# 07_WI-FI.net
KiCad netlist of a schematic drawn in Altium Designer
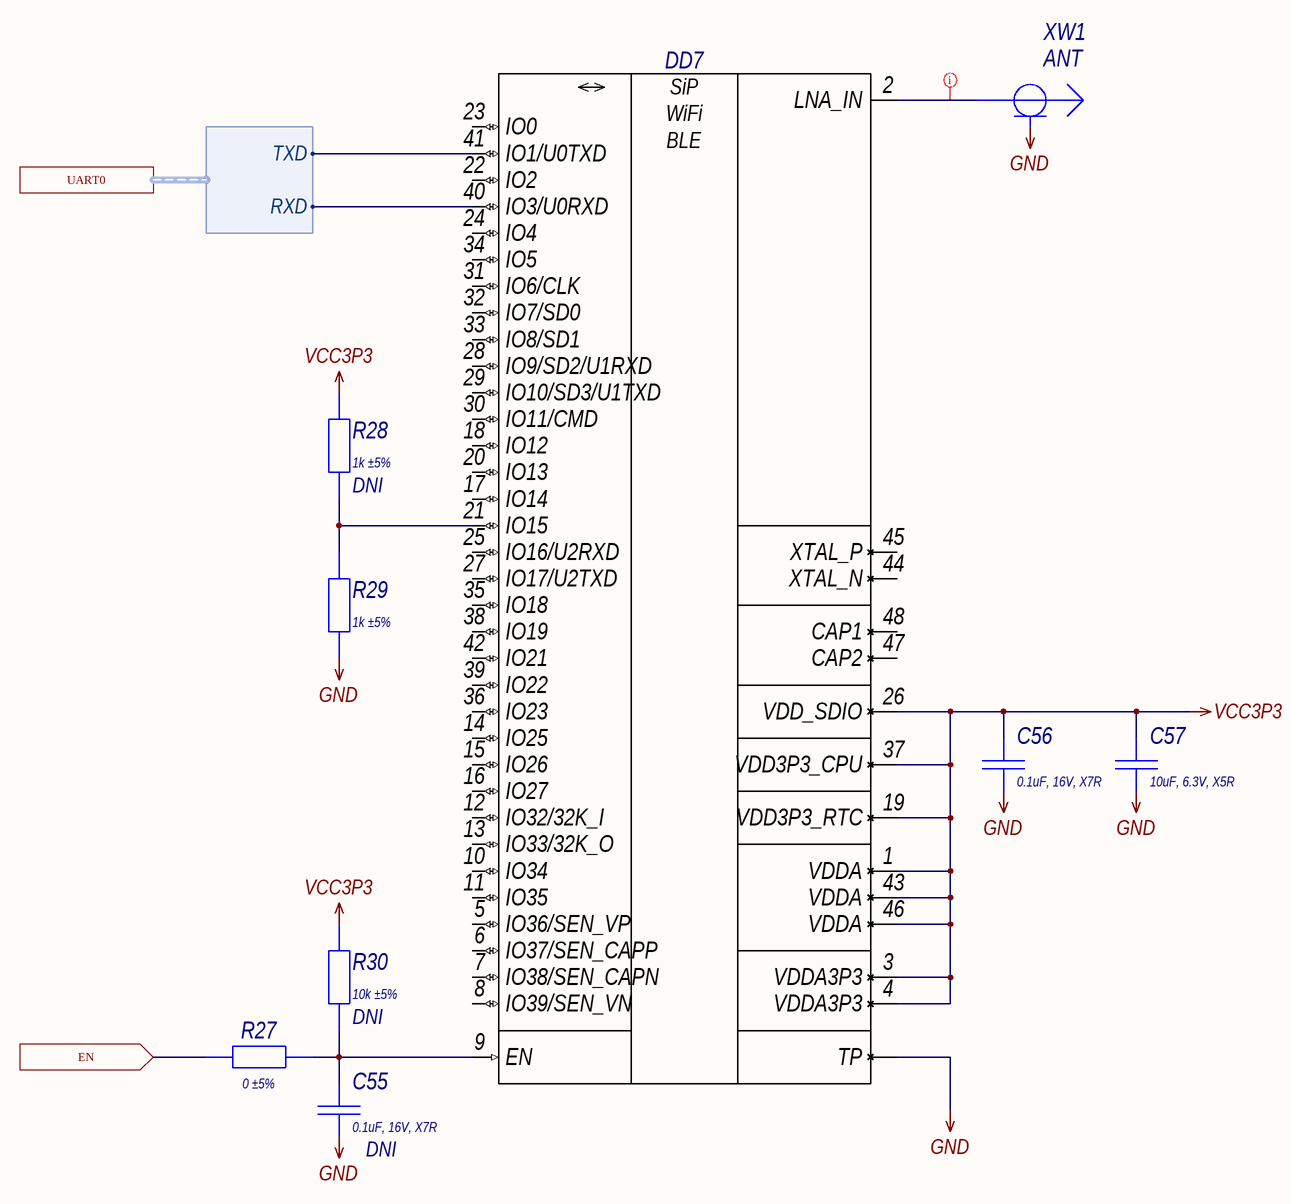
[diagram p0: 07_WI-FI.SchDoc]

(export (version "E")
  (design (tool "Eeschema 10.0.6"))
  (components
    (comp (ref "C55")
      (value "Capacitor")
      (footprint "C0402_L")
      (fields
        (field (name "SCHEMATIC VALUE") "0.1uF, 16V, X7R")
        (field (name "PART NUMBER") "GCM155R71C104KA55D")
        (field (name "VOLTAGE") "16V")
        (field (name "TOLERANCE") "±10%")
        (field (name "PUBLISHER") "Andrew Danich")
      )
      (libsource (lib "ADLib") (part "Capacitor"))
    )
    (comp (ref "C56")
      (value "Capacitor")
      (footprint "C0402_L")
      (fields
        (field (name "SCHEMATIC VALUE") "0.1uF, 16V, X7R")
        (field (name "PART NUMBER") "GCM155R71C104KA55D")
        (field (name "VOLTAGE") "16V")
        (field (name "TOLERANCE") "±10%")
        (field (name "PUBLISHER") "Andrew Danich")
      )
      (libsource (lib "ADLib") (part "Capacitor"))
    )
    (comp (ref "C57")
      (value "Capacitor")
      (footprint "C0402_L")
      (fields
        (field (name "SCHEMATIC VALUE") "10uF, 6.3V, X5R")
        (field (name "PART NUMBER") "GRM155R60J106ME15D")
        (field (name "VOLTAGE") "6.3V")
        (field (name "TOLERANCE") "±20%")
        (field (name "PUBLISHER") "Andrew Danich")
      )
      (libsource (lib "ADLib") (part "Capacitor"))
    )
    (comp (ref "DD7")
      (value "ESP32-PICO-D4")
      (footprint "QFN-48_050P700X700X104_N")
      (fields (field (name "MANUFACTURER") "Espressif Systems") (field (name "PUBLISHER") "Andrew Danich"))
      (libsource (lib "ADLib") (part "ESP32-PICO-D4"))
    )
    (comp (ref "R27")
      (value "Resistor")
      (footprint "R0402_L")
      (fields
        (field (name "SCHEMATIC VALUE") "0 ±5%")
        (field (name "PART NUMBER") "RC0402JR-070RL")
        (field (name "TOLERANCE") "±5%")
        (field (name "MANUFACTURER") "Yageo")
        (field (name "PUBLISHER") "Andrew Danich")
      )
      (libsource (lib "ADLib") (part "Resistor"))
    )
    (comp (ref "R28")
      (value "Resistor")
      (footprint "R0402_L")
      (fields
        (field (name "SCHEMATIC VALUE") "1k ±5%")
        (field (name "PART NUMBER") "RC0402JR-071KL")
        (field (name "TOLERANCE") "±5%")
        (field (name "MANUFACTURER") "Yageo")
        (field (name "PUBLISHER") "Andrew Danich")
      )
      (libsource (lib "ADLib") (part "Resistor"))
    )
    (comp (ref "R29")
      (value "Resistor")
      (footprint "R0402_L")
      (fields
        (field (name "SCHEMATIC VALUE") "1k ±5%")
        (field (name "PART NUMBER") "RC0402JR-071KL")
        (field (name "TOLERANCE") "±5%")
        (field (name "MANUFACTURER") "Yageo")
        (field (name "PUBLISHER") "Andrew Danich")
      )
      (libsource (lib "ADLib") (part "Resistor"))
    )
    (comp (ref "R30")
      (value "Resistor")
      (footprint "R0402_L")
      (fields
        (field (name "SCHEMATIC VALUE") "10k ±5%")
        (field (name "PART NUMBER") "RC0402JR-0710KL")
        (field (name "TOLERANCE") "±5%")
        (field (name "MANUFACTURER") "Yageo")
        (field (name "PUBLISHER") "Andrew Danich")
      )
      (libsource (lib "ADLib") (part "Resistor"))
    )
    (comp (ref "XW1")
      (value "ANT")
      (footprint "1909763-1")
      (fields
        (field (name "PART NUMBER") "1909763-1")
        (field (name "MANUFACTURER") "TE Connectivity")
        (field (name "PUBLISHER") "НТЦ \"Вектор\"")
      )
      (libsource (lib "ADLib") (part "Con-RF-M"))
    )
  )
  (nets
    (net (code "2") (name "/EN") (class "Default")
      (node (ref "R27") (pin "1") (pinfunction "1_1") (pintype "passive"))
    )
    (net (code "3") (name "/RXD") (class "Default")
      (node (ref "DD7") (pin "40") (pinfunction "IO3/U0RXD_40") (pintype "bidirectional"))
    )
    (net (code "4") (name "/TXD") (class "Default")
      (node (ref "DD7") (pin "41") (pinfunction "IO1/U0TXD_41") (pintype "bidirectional"))
    )
    (net (code "6") (name "GND") (class "Default")
      (node (ref "C55") (pin "1") (pinfunction "1_1") (pintype "passive"))
      (node (ref "C56") (pin "1") (pinfunction "1_1") (pintype "passive"))
      (node (ref "C57") (pin "1") (pinfunction "1_1") (pintype "passive"))
      (node (ref "DD7") (pin "TP") (pinfunction "TP_TP") (pintype "power_in"))
      (node (ref "R29") (pin "1") (pinfunction "1_1") (pintype "passive"))
      (node (ref "XW1") (pin "2") (pintype "passive"))
    )
    (net (code "7") (name "Net-(DD7-EN)") (class "Default")
      (node (ref "C55") (pin "2") (pinfunction "2_2") (pintype "passive"))
      (node (ref "DD7") (pin "9") (pinfunction "EN_9") (pintype "input"))
      (node (ref "R27") (pin "2") (pinfunction "2_2") (pintype "passive"))
      (node (ref "R30") (pin "1") (pinfunction "1_1") (pintype "passive"))
    )
    (net (code "8") (name "Net-(DD7-IO15)") (class "Default")
      (node (ref "DD7") (pin "21") (pinfunction "IO15_21") (pintype "bidirectional"))
      (node (ref "R28") (pin "1") (pinfunction "1_1") (pintype "passive"))
      (node (ref "R29") (pin "2") (pinfunction "2_2") (pintype "passive"))
    )
    (net (code "9") (name "Net-(DD7-LNA_IN)") (class "Default")
      (node (ref "DD7") (pin "2") (pinfunction "LNA_IN_2") (pintype "passive"))
      (node (ref "XW1") (pin "1") (pintype "passive"))
    )
    (net (code "10") (name "VCC3P3") (class "Default")
      (node (ref "C56") (pin "2") (pinfunction "2_2") (pintype "passive"))
      (node (ref "C57") (pin "2") (pinfunction "2_2") (pintype "passive"))
      (node (ref "DD7") (pin "1") (pinfunction "VDDA_1") (pintype "power_in"))
      (node (ref "DD7") (pin "19") (pinfunction "VDD3P3_RTC_19") (pintype "power_in"))
      (node (ref "DD7") (pin "26") (pinfunction "VDD_SDIO_26") (pintype "power_in"))
      (node (ref "DD7") (pin "3") (pinfunction "VDDA3P3_3") (pintype "power_in"))
      (node (ref "DD7") (pin "37") (pinfunction "VDD3P3_CPU_37") (pintype "power_in"))
      (node (ref "DD7") (pin "4") (pinfunction "VDDA3P3_4") (pintype "power_in"))
      (node (ref "DD7") (pin "43") (pinfunction "VDDA_43") (pintype "power_in"))
      (node (ref "DD7") (pin "46") (pinfunction "VDDA_46") (pintype "power_in"))
      (node (ref "R28") (pin "2") (pinfunction "2_2") (pintype "passive"))
      (node (ref "R30") (pin "2") (pinfunction "2_2") (pintype "passive"))
    )
    (net (code "11") (name "unconnected-(DD7-CAP1-Pad48)") (class "Default")
      (node (ref "DD7") (pin "48") (pinfunction "CAP1_48") (pintype "passive"))
    )
    (net (code "12") (name "unconnected-(DD7-CAP2-Pad47)") (class "Default")
      (node (ref "DD7") (pin "47") (pinfunction "CAP2_47") (pintype "passive"))
    )
    (net (code "13") (name "unconnected-(DD7-IO0-Pad23)") (class "Default")
      (node (ref "DD7") (pin "23") (pinfunction "IO0_23") (pintype "bidirectional"))
    )
    (net (code "14") (name "unconnected-(DD7-IO2-Pad22)") (class "Default")
      (node (ref "DD7") (pin "22") (pinfunction "IO2_22") (pintype "bidirectional"))
    )
    (net (code "15") (name "unconnected-(DD7-IO4-Pad24)") (class "Default")
      (node (ref "DD7") (pin "24") (pinfunction "IO4_24") (pintype "bidirectional"))
    )
    (net (code "16") (name "unconnected-(DD7-IO5-Pad34)") (class "Default")
      (node (ref "DD7") (pin "34") (pinfunction "IO5_34") (pintype "bidirectional"))
    )
    (net (code "17") (name "unconnected-(DD7-IO6{slash}CLK-Pad31)") (class "Default")
      (node (ref "DD7") (pin "31") (pinfunction "IO6/CLK_31") (pintype "bidirectional"))
    )
    (net (code "18") (name "unconnected-(DD7-IO7{slash}SD0-Pad32)") (class "Default")
      (node (ref "DD7") (pin "32") (pinfunction "IO7/SD0_32") (pintype "bidirectional"))
    )
    (net (code "19") (name "unconnected-(DD7-IO8{slash}SD1-Pad33)") (class "Default")
      (node (ref "DD7") (pin "33") (pinfunction "IO8/SD1_33") (pintype "bidirectional"))
    )
    (net (code "20") (name "unconnected-(DD7-IO9{slash}SD2{slash}U1RXD-Pad28)") (class "Default")
      (node (ref "DD7") (pin "28") (pinfunction "IO9/SD2/U1RXD_28") (pintype "bidirectional"))
    )
    (net (code "21") (name "unconnected-(DD7-IO10{slash}SD3{slash}U1TXD-Pad29)") (class "Default")
      (node (ref "DD7") (pin "29") (pinfunction "IO10/SD3/U1TXD_29") (pintype "bidirectional"))
    )
    (net (code "22") (name "unconnected-(DD7-IO11{slash}CMD-Pad30)") (class "Default")
      (node (ref "DD7") (pin "30") (pinfunction "IO11/CMD_30") (pintype "bidirectional"))
    )
    (net (code "23") (name "unconnected-(DD7-IO12-Pad18)") (class "Default")
      (node (ref "DD7") (pin "18") (pinfunction "IO12_18") (pintype "bidirectional"))
    )
    (net (code "24") (name "unconnected-(DD7-IO13-Pad20)") (class "Default")
      (node (ref "DD7") (pin "20") (pinfunction "IO13_20") (pintype "bidirectional"))
    )
    (net (code "25") (name "unconnected-(DD7-IO14-Pad17)") (class "Default")
      (node (ref "DD7") (pin "17") (pinfunction "IO14_17") (pintype "bidirectional"))
    )
    (net (code "26") (name "unconnected-(DD7-IO16{slash}U2RXD-Pad25)") (class "Default")
      (node (ref "DD7") (pin "25") (pinfunction "IO16/U2RXD_25") (pintype "bidirectional"))
    )
    (net (code "27") (name "unconnected-(DD7-IO17{slash}U2TXD-Pad27)") (class "Default")
      (node (ref "DD7") (pin "27") (pinfunction "IO17/U2TXD_27") (pintype "bidirectional"))
    )
    (net (code "28") (name "unconnected-(DD7-IO18-Pad35)") (class "Default")
      (node (ref "DD7") (pin "35") (pinfunction "IO18_35") (pintype "bidirectional"))
    )
    (net (code "29") (name "unconnected-(DD7-IO19-Pad38)") (class "Default")
      (node (ref "DD7") (pin "38") (pinfunction "IO19_38") (pintype "bidirectional"))
    )
    (net (code "30") (name "unconnected-(DD7-IO21-Pad42)") (class "Default")
      (node (ref "DD7") (pin "42") (pinfunction "IO21_42") (pintype "bidirectional"))
    )
    (net (code "31") (name "unconnected-(DD7-IO22-Pad39)") (class "Default")
      (node (ref "DD7") (pin "39") (pinfunction "IO22_39") (pintype "bidirectional"))
    )
    (net (code "32") (name "unconnected-(DD7-IO23-Pad36)") (class "Default")
      (node (ref "DD7") (pin "36") (pinfunction "IO23_36") (pintype "bidirectional"))
    )
    (net (code "33") (name "unconnected-(DD7-IO25-Pad14)") (class "Default")
      (node (ref "DD7") (pin "14") (pinfunction "IO25_14") (pintype "bidirectional"))
    )
    (net (code "34") (name "unconnected-(DD7-IO26-Pad15)") (class "Default")
      (node (ref "DD7") (pin "15") (pinfunction "IO26_15") (pintype "bidirectional"))
    )
    (net (code "35") (name "unconnected-(DD7-IO27-Pad16)") (class "Default")
      (node (ref "DD7") (pin "16") (pinfunction "IO27_16") (pintype "bidirectional"))
    )
    (net (code "36") (name "unconnected-(DD7-IO32{slash}32K_I-Pad12)") (class "Default")
      (node (ref "DD7") (pin "12") (pinfunction "IO32/32K_I_12") (pintype "bidirectional"))
    )
    (net (code "37") (name "unconnected-(DD7-IO33{slash}32K_O-Pad13)") (class "Default")
      (node (ref "DD7") (pin "13") (pinfunction "IO33/32K_O_13") (pintype "bidirectional"))
    )
    (net (code "38") (name "unconnected-(DD7-IO34-Pad10)") (class "Default")
      (node (ref "DD7") (pin "10") (pinfunction "IO34_10") (pintype "bidirectional"))
    )
    (net (code "39") (name "unconnected-(DD7-IO35-Pad11)") (class "Default")
      (node (ref "DD7") (pin "11") (pinfunction "IO35_11") (pintype "bidirectional"))
    )
    (net (code "40") (name "unconnected-(DD7-IO36{slash}SEN_VP-Pad5)") (class "Default")
      (node (ref "DD7") (pin "5") (pinfunction "IO36/SEN_VP_5") (pintype "bidirectional"))
    )
    (net (code "41") (name "unconnected-(DD7-IO37{slash}SEN_CAPP-Pad6)") (class "Default")
      (node (ref "DD7") (pin "6") (pinfunction "IO37/SEN_CAPP_6") (pintype "bidirectional"))
    )
    (net (code "42") (name "unconnected-(DD7-IO38{slash}SEN_CAPN-Pad7)") (class "Default")
      (node (ref "DD7") (pin "7") (pinfunction "IO38/SEN_CAPN_7") (pintype "bidirectional"))
    )
    (net (code "43") (name "unconnected-(DD7-IO39{slash}SEN_VN-Pad8)") (class "Default")
      (node (ref "DD7") (pin "8") (pinfunction "IO39/SEN_VN_8") (pintype "bidirectional"))
    )
    (net (code "44") (name "unconnected-(DD7-XTAL_N-Pad44)") (class "Default")
      (node (ref "DD7") (pin "44") (pinfunction "XTAL_N_44") (pintype "passive"))
    )
    (net (code "45") (name "unconnected-(DD7-XTAL_P-Pad45)") (class "Default")
      (node (ref "DD7") (pin "45") (pinfunction "XTAL_P_45") (pintype "passive"))
    )
  )
)
